# fabflash-mk-2_3-battcon-flattened.net
KiCad netlist of a schematic drawn in EAGLE
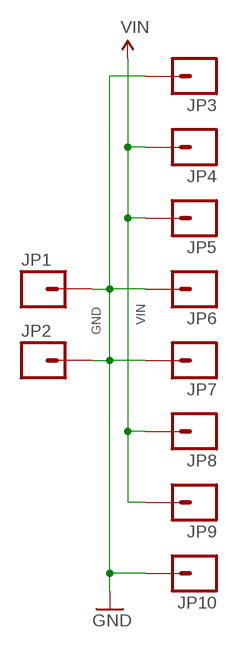
[diagram p0: schematic, sheet 1]

(export (version "E")
  (design (tool "Eeschema 10.0.6"))
  (components
    (comp (ref "JP1")
      (value "M01NOT-A-VIA-NOPE")
      (footprint "eagle-import:1X01_NOSILK_NOSTOP")
      (libsource (lib "eagle-import") (part "M01NOT-A-VIA-NOPE"))
    )
    (comp (ref "JP2")
      (value "M01NOT-A-VIA-NOPE")
      (footprint "eagle-import:1X01_NOSILK_NOSTOP")
      (libsource (lib "eagle-import") (part "M01NOT-A-VIA-NOPE"))
    )
    (comp (ref "JP3")
      (value "M01SMD-1X2.5MM-NS")
      (footprint "eagle-import:1X01-SMD-1X2.5MM-NS")
      (libsource (lib "eagle-import") (part "M01SMD-1X2.5MM-NS"))
    )
    (comp (ref "JP4")
      (value "M01NOSILK-KIT")
      (footprint "eagle-import:1X01NS-KIT")
      (libsource (lib "eagle-import") (part "M01NOSILK-KIT"))
    )
    (comp (ref "JP5")
      (value "M01NOSILK-KIT")
      (footprint "eagle-import:1X01NS-KIT")
      (libsource (lib "eagle-import") (part "M01NOSILK-KIT"))
    )
    (comp (ref "JP6")
      (value "M01SMD-1X2.5MM-NS")
      (footprint "eagle-import:1X01-SMD-1X2.5MM-NS")
      (libsource (lib "eagle-import") (part "M01SMD-1X2.5MM-NS"))
    )
    (comp (ref "JP7")
      (value "M01SMD-1X2.5MM-NS")
      (footprint "eagle-import:1X01-SMD-1X2.5MM-NS")
      (libsource (lib "eagle-import") (part "M01SMD-1X2.5MM-NS"))
    )
    (comp (ref "JP8")
      (value "M01NOSILK-KIT")
      (footprint "eagle-import:1X01NS-KIT")
      (libsource (lib "eagle-import") (part "M01NOSILK-KIT"))
    )
    (comp (ref "JP9")
      (value "M01NOSILK-KIT")
      (footprint "eagle-import:1X01NS-KIT")
      (libsource (lib "eagle-import") (part "M01NOSILK-KIT"))
    )
    (comp (ref "JP10")
      (value "M01SMD-1X2.5MM-NS")
      (footprint "eagle-import:1X01-SMD-1X2.5MM-NS")
      (libsource (lib "eagle-import") (part "M01SMD-1X2.5MM-NS"))
    )
  )
  (nets
    (net (code "1") (name "GND") (class "Default")
      (node (ref "JP1") (pin "P$1") (pinfunction "1_P$1") (pintype "passive"))
      (node (ref "JP10") (pin "1") (pinfunction "1_1") (pintype "passive"))
      (node (ref "JP2") (pin "P$1") (pinfunction "1_P$1") (pintype "passive"))
      (node (ref "JP3") (pin "1") (pinfunction "1_1") (pintype "passive"))
      (node (ref "JP6") (pin "1") (pinfunction "1_1") (pintype "passive"))
      (node (ref "JP7") (pin "1") (pinfunction "1_1") (pintype "passive"))
    )
    (net (code "2") (name "VIN") (class "Default")
      (node (ref "JP4") (pin "1") (pinfunction "1_1") (pintype "passive"))
      (node (ref "JP5") (pin "1") (pinfunction "1_1") (pintype "passive"))
      (node (ref "JP8") (pin "1") (pinfunction "1_1") (pintype "passive"))
      (node (ref "JP9") (pin "1") (pinfunction "1_1") (pintype "passive"))
    )
  )
)
